# STM32.net
KiCad netlist of a schematic drawn in Altium Designer
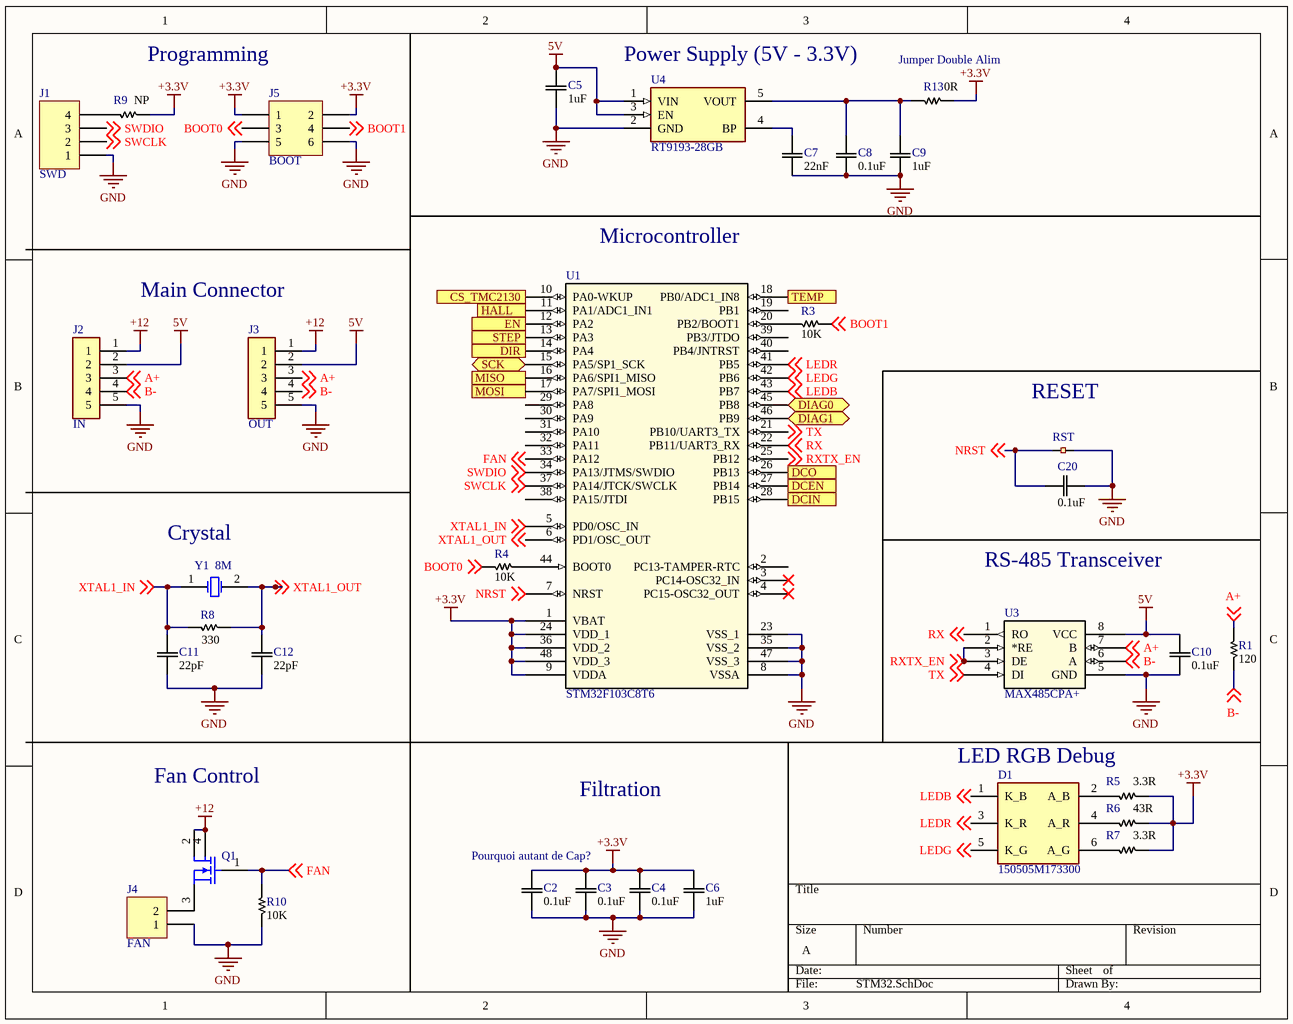
[diagram p0: STM32.SchDoc]

(export (version "E")
  (design (tool "Eeschema 10.0.6"))
  (components
    (comp (ref "C2")
      (value "0.1uF")
      (footprint "0603")
      (description "Capacitor SMD 1206")
      (fields
        (field (name "MANUFACTURER_PART_NUMBER") "12065A820JAT2A")
        (field (name "Comment") "Capacitor 1206")
        (field (name "COPYRIGHT") "Copyright (C) 2018 Accelerated Designs. All rights reserved")
      )
      (libsource (lib "Schematic_Emile") (part "Capacitor 1206"))
    )
    (comp (ref "C3")
      (value "0.1uF")
      (footprint "0603")
      (description "Capacitor SMD 1206")
      (fields
        (field (name "MANUFACTURER_PART_NUMBER") "12065A820JAT2A")
        (field (name "Comment") "Capacitor 1206")
        (field (name "COPYRIGHT") "Copyright (C) 2018 Accelerated Designs. All rights reserved")
      )
      (libsource (lib "Schematic_Emile") (part "Capacitor 1206"))
    )
    (comp (ref "C4")
      (value "0.1uF")
      (footprint "0603")
      (description "Capacitor SMD 1206")
      (fields
        (field (name "MANUFACTURER_PART_NUMBER") "12065A820JAT2A")
        (field (name "Comment") "Capacitor 1206")
        (field (name "COPYRIGHT") "Copyright (C) 2018 Accelerated Designs. All rights reserved")
      )
      (libsource (lib "Schematic_Emile") (part "Capacitor 1206"))
    )
    (comp (ref "C5")
      (value "1uF")
      (footprint "0603")
      (description "Capacitor SMD 1206")
      (fields
        (field (name "MANUFACTURER_PART_NUMBER") "12065A820JAT2A")
        (field (name "Comment") "Capacitor 1206")
        (field (name "COPYRIGHT") "Copyright (C) 2018 Accelerated Designs. All rights reserved")
      )
      (libsource (lib "Schematic_Emile") (part "Capacitor 1206"))
    )
    (comp (ref "C6")
      (value "1uF")
      (footprint "0603")
      (description "Capacitor SMD 1206")
      (fields
        (field (name "MANUFACTURER_PART_NUMBER") "12065A820JAT2A")
        (field (name "Comment") "Capacitor 1206")
        (field (name "COPYRIGHT") "Copyright (C) 2018 Accelerated Designs. All rights reserved")
      )
      (libsource (lib "Schematic_Emile") (part "Capacitor 1206"))
    )
    (comp (ref "C7")
      (value "22nF")
      (footprint "0603")
      (description "Capacitor SMD 1206")
      (fields
        (field (name "MANUFACTURER_PART_NUMBER") "12065A820JAT2A")
        (field (name "Comment") "Capacitor 1206")
        (field (name "COPYRIGHT") "Copyright (C) 2018 Accelerated Designs. All rights reserved")
      )
      (libsource (lib "Schematic_Emile") (part "Capacitor 1206"))
    )
    (comp (ref "C8")
      (value "0.1uF")
      (footprint "0603")
      (description "Capacitor SMD 1206")
      (fields
        (field (name "MANUFACTURER_PART_NUMBER") "12065A820JAT2A")
        (field (name "Comment") "Capacitor 1206")
        (field (name "COPYRIGHT") "Copyright (C) 2018 Accelerated Designs. All rights reserved")
      )
      (libsource (lib "Schematic_Emile") (part "Capacitor 1206"))
    )
    (comp (ref "C9")
      (value "1uF")
      (footprint "0603")
      (description "Capacitor SMD 1206")
      (fields
        (field (name "MANUFACTURER_PART_NUMBER") "12065A820JAT2A")
        (field (name "Comment") "Capacitor 1206")
        (field (name "COPYRIGHT") "Copyright (C) 2018 Accelerated Designs. All rights reserved")
      )
      (libsource (lib "Schematic_Emile") (part "Capacitor 1206"))
    )
    (comp (ref "C10")
      (value "0.1uF")
      (footprint "0603")
      (description "Capacitor SMD 1206")
      (fields
        (field (name "MANUFACTURER_PART_NUMBER") "12065A820JAT2A")
        (field (name "Comment") "Capacitor 1206")
        (field (name "COPYRIGHT") "Copyright (C) 2018 Accelerated Designs. All rights reserved")
      )
      (libsource (lib "Schematic_Emile") (part "Capacitor 1206"))
    )
    (comp (ref "C11")
      (value "22pF")
      (footprint "0603")
      (description "Capacitor SMD 1206")
      (fields
        (field (name "MANUFACTURER_PART_NUMBER") "12065A820JAT2A")
        (field (name "Comment") "Capacitor 1206")
        (field (name "COPYRIGHT") "Copyright (C) 2018 Accelerated Designs. All rights reserved")
      )
      (libsource (lib "Schematic_Emile") (part "Capacitor 1206"))
    )
    (comp (ref "C12")
      (value "22pF")
      (footprint "0603")
      (description "Capacitor SMD 1206")
      (fields
        (field (name "MANUFACTURER_PART_NUMBER") "12065A820JAT2A")
        (field (name "Comment") "Capacitor 1206")
        (field (name "COPYRIGHT") "Copyright (C) 2018 Accelerated Designs. All rights reserved")
      )
      (libsource (lib "Schematic_Emile") (part "Capacitor 1206"))
    )
    (comp (ref "C20")
      (value "0.1uF")
      (footprint "0603")
      (description "Capacitor SMD 1206")
      (fields
        (field (name "MANUFACTURER_PART_NUMBER") "12065A820JAT2A")
        (field (name "Comment") "Capacitor 1206")
        (field (name "COPYRIGHT") "Copyright (C) 2018 Accelerated Designs. All rights reserved")
      )
      (libsource (lib "Schematic_Emile") (part "Capacitor 1206"))
    )
    (comp (ref "D1")
      (value "150505M173300")
      (footprint "LED 5050")
      (description "LED")
      (fields
        (field (name "MOUSER PART NUMBER") "710-150505M173300")
        (field (name "RS PART NUMBER") "1766248P")
      )
      (libsource (lib "Schematic_Emile") (part "150505M173300"))
    )
    (comp (ref "J1")
      (value "SWD")
      (footprint "HDR1X4")
      (description "Header, 4-Pin")
      (fields (field (name "PUBLISHER") "Altium Limited"))
      (libsource (lib "Miscellaneous Connectors") (part "Header 4"))
    )
    (comp (ref "J2")
      (value "IN")
      (footprint "JST 5POS 2.5mm 90°")
      (description "Connector")
      (fields (field (name "MANUFACTURER_PART_NUMBER") "S5B-XH-A-1(LF)(SN)"))
      (libsource (lib "Schematic_Emile") (part "JST 5POS"))
    )
    (comp (ref "J3")
      (value "OUT")
      (footprint "JST 5POS 2.5mm 90°")
      (description "Connector")
      (fields (field (name "MANUFACTURER_PART_NUMBER") "S5B-XH-A-1(LF)(SN)"))
      (libsource (lib "Schematic_Emile") (part "JST 5POS"))
    )
    (comp (ref "J4")
      (value "FAN")
      (footprint "HDR1X2")
      (description "Header, 2-Pin")
      (fields (field (name "PUBLISHER") "Altium Limited"))
      (libsource (lib "Miscellaneous Connectors") (part "Header 2"))
    )
    (comp (ref "J5")
      (value "BOOT")
      (footprint "HDR2X3")
      (description "Header, 3-Pin, Dual row")
      (fields (field (name "PUBLISHER") "Altium Limited"))
      (libsource (lib "Miscellaneous Connectors") (part "Header 3X2"))
    )
    (comp (ref "Q1")
      (value "MOSFET N-CH")
      (footprint "SOT223_M")
      (description "55V 7A SOT223")
      (libsource (lib "Schematic_Emile") (part "MOSFET N-CH"))
    )
    (comp (ref "R1")
      (value "120")
      (footprint "0603")
      (description "Resistor 0603 SMD")
      (fields
        (field (name "MANUFACTURER_PART_NUMBER") "ERJ8CWFR024V")
        (field (name "Comment") "Resistor 0603")
        (field (name "COPYRIGHT") "Copyright (C) 2018 Accelerated Designs. All rights reserved")
      )
      (libsource (lib "Schematic_Emile") (part "Resistor 1206"))
    )
    (comp (ref "R3")
      (value "10K")
      (footprint "0603")
      (description "Resistor 1206 SMD")
      (fields
        (field (name "MANUFACTURER_PART_NUMBER") "ERJ8CWFR024V")
        (field (name "Comment") "Resistor 1206")
        (field (name "COPYRIGHT") "Copyright (C) 2018 Accelerated Designs. All rights reserved")
      )
      (libsource (lib "Schematic_Emile") (part "Resistor 1206"))
    )
    (comp (ref "R4")
      (value "10K")
      (footprint "0603")
      (description "Resistor 1206 SMD")
      (fields
        (field (name "MANUFACTURER_PART_NUMBER") "ERJ8CWFR024V")
        (field (name "Comment") "Resistor 1206")
        (field (name "COPYRIGHT") "Copyright (C) 2018 Accelerated Designs. All rights reserved")
      )
      (libsource (lib "Schematic_Emile") (part "Resistor 1206"))
    )
    (comp (ref "R5")
      (value "3.3R")
      (footprint "0603")
      (description "Resistor 0603 SMD")
      (fields
        (field (name "MANUFACTURER_PART_NUMBER") "ERJ8CWFR024V")
        (field (name "Comment") "Resistor 0603")
        (field (name "COPYRIGHT") "Copyright (C) 2018 Accelerated Designs. All rights reserved")
      )
      (libsource (lib "Schematic_Emile") (part "Resistor 1206"))
    )
    (comp (ref "R6")
      (value "43R")
      (footprint "0603")
      (description "Resistor 0603 SMD")
      (fields
        (field (name "MANUFACTURER_PART_NUMBER") "ERJ8CWFR024V")
        (field (name "Comment") "Resistor 0603")
        (field (name "COPYRIGHT") "Copyright (C) 2018 Accelerated Designs. All rights reserved")
      )
      (libsource (lib "Schematic_Emile") (part "Resistor 1206"))
    )
    (comp (ref "R7")
      (value "3.3R")
      (footprint "0603")
      (description "Resistor 0603 SMD")
      (fields
        (field (name "MANUFACTURER_PART_NUMBER") "ERJ8CWFR024V")
        (field (name "Comment") "Resistor 0603")
        (field (name "COPYRIGHT") "Copyright (C) 2018 Accelerated Designs. All rights reserved")
      )
      (libsource (lib "Schematic_Emile") (part "Resistor 1206"))
    )
    (comp (ref "R8")
      (value "330")
      (footprint "0603")
      (description "Resistor 0603 SMD")
      (fields
        (field (name "MANUFACTURER_PART_NUMBER") "ERJ8CWFR024V")
        (field (name "Comment") "Resistor 0603")
        (field (name "COPYRIGHT") "Copyright (C) 2018 Accelerated Designs. All rights reserved")
      )
      (libsource (lib "Schematic_Emile") (part "Resistor 1206"))
    )
    (comp (ref "R9")
      (value "NP")
      (footprint "0603")
      (description "Resistor 1206 SMD")
      (fields
        (field (name "MANUFACTURER_PART_NUMBER") "ERJ8CWFR024V")
        (field (name "Comment") "Jumper 0603")
        (field (name "COPYRIGHT") "Copyright (C) 2018 Accelerated Designs. All rights reserved")
      )
      (libsource (lib "Schematic_Emile") (part "Resistor 1206"))
    )
    (comp (ref "R10")
      (value "10K")
      (footprint "0603")
      (description "Resistor 0603 SMD")
      (fields
        (field (name "MANUFACTURER_PART_NUMBER") "ERJ8CWFR024V")
        (field (name "Comment") "Resistor 0603")
        (field (name "COPYRIGHT") "Copyright (C) 2018 Accelerated Designs. All rights reserved")
      )
      (libsource (lib "Schematic_Emile") (part "Resistor 1206"))
    )
    (comp (ref "R13")
      (value "0R")
      (footprint "0603")
      (description "Resistor 1206 SMD")
      (fields
        (field (name "MANUFACTURER_PART_NUMBER") "ERJ8CWFR024V")
        (field (name "Comment") "Jumper 0603")
        (field (name "COPYRIGHT") "Copyright (C) 2018 Accelerated Designs. All rights reserved")
      )
      (libsource (lib "Schematic_Emile") (part "Resistor 1206"))
    )
    (comp (ref "RST")
      (value "PAD")
      (footprint "PAD")
      (description "SMD Pad for contact")
      (libsource (lib "Schematic_Emile") (part "PAD"))
    )
    (comp (ref "U1")
      (value "STM32F103C8T6")
      (footprint "LQFP-48")
      (description "Integrated Circuit STM32")
      (fields (field (name "COPYRIGHT") "Copyright (C) 2018 Accelerated Designs. All rights reserved"))
      (libsource (lib "Schematic_Emile") (part "STM32F103C8T6"))
    )
    (comp (ref "U3")
      (value "MAX485CPA+")
      (footprint "DIP 8 - 3D")
      (description "RS485 Communication")
      (fields (field (name "COPYRIGHT") "Copyright (C) 2018 Accelerated Designs. All rights reserved"))
      (libsource (lib "Schematic_Emile") (part "MAX485CPA+"))
    )
    (comp (ref "U4")
      (value "RT9193-28GB")
      (footprint "SamacSys:SOT94P279X130-5N")
      (description "Voltage Regulator 3.3V")
      (libsource (lib "Schematic_Emile") (part "RT9193-28GB"))
    )
    (comp (ref "Y1")
      (value "8M")
      (footprint "ATS080B-E")
      (description "Crystal Oscillator")
      (fields (field (name "PUBLISHER") "Altium Limited"))
      (libsource (lib "Miscellaneous Devices") (part "XTAL"))
    )
  )
  (nets
    (net (code "1") (name "+3.3V") (class "Default")
      (node (ref "C2") (pin "2") (pinfunction "2_2") (pintype "passive"))
      (node (ref "C3") (pin "2") (pinfunction "2_2") (pintype "passive"))
      (node (ref "C4") (pin "2") (pinfunction "2_2") (pintype "passive"))
      (node (ref "C6") (pin "2") (pinfunction "2_2") (pintype "passive"))
      (node (ref "J5") (pin "1") (pinfunction "1_1") (pintype "passive"))
      (node (ref "J5") (pin "2") (pinfunction "2_2") (pintype "passive"))
      (node (ref "R13") (pin "2") (pinfunction "2_2") (pintype "passive"))
      (node (ref "R5") (pin "2") (pinfunction "2_2") (pintype "passive"))
      (node (ref "R6") (pin "2") (pinfunction "2_2") (pintype "passive"))
      (node (ref "R7") (pin "2") (pinfunction "2_2") (pintype "passive"))
      (node (ref "R9") (pin "2") (pinfunction "2_2") (pintype "passive"))
      (node (ref "U1") (pin "1") (pinfunction "VBAT_1") (pintype "power_in"))
      (node (ref "U1") (pin "24") (pinfunction "VDD_1_24") (pintype "power_in"))
      (node (ref "U1") (pin "36") (pinfunction "VDD_2_36") (pintype "power_in"))
      (node (ref "U1") (pin "48") (pinfunction "VDD_3_48") (pintype "power_in"))
      (node (ref "U1") (pin "9") (pinfunction "VDDA_9") (pintype "power_in"))
    )
    (net (code "2") (name "+12") (class "Default")
      (node (ref "J2") (pin "1") (pinfunction "1_1") (pintype "passive"))
      (node (ref "J3") (pin "1") (pinfunction "1_1") (pintype "passive"))
      (node (ref "Q1") (pin "2") (pinfunction "D_2") (pintype "passive"))
      (node (ref "Q1") (pin "4") (pinfunction "D_4") (pintype "passive"))
    )
    (net (code "3") (name "/CS_TMC2130") (class "Default")
      (node (ref "U1") (pin "10") (pinfunction "PA0-WKUP_10") (pintype "bidirectional"))
    )
    (net (code "4") (name "/DCEN") (class "Default")
      (node (ref "U1") (pin "27") (pinfunction "PB14_27") (pintype "bidirectional"))
    )
    (net (code "5") (name "/DCIN") (class "Default")
      (node (ref "U1") (pin "28") (pinfunction "PB15_28") (pintype "bidirectional"))
    )
    (net (code "6") (name "/DCO") (class "Default")
      (node (ref "U1") (pin "26") (pinfunction "PB13_26") (pintype "bidirectional"))
    )
    (net (code "7") (name "/DIAG0") (class "Default")
      (node (ref "U1") (pin "45") (pinfunction "PB8_45") (pintype "bidirectional"))
    )
    (net (code "8") (name "/DIAG1") (class "Default")
      (node (ref "U1") (pin "46") (pinfunction "PB9_46") (pintype "bidirectional"))
    )
    (net (code "9") (name "/DIR") (class "Default")
      (node (ref "U1") (pin "14") (pinfunction "PA4_14") (pintype "bidirectional"))
    )
    (net (code "10") (name "/EN") (class "Default")
      (node (ref "U1") (pin "12") (pinfunction "PA2_12") (pintype "bidirectional"))
    )
    (net (code "11") (name "/HALL") (class "Default")
      (node (ref "U1") (pin "11") (pinfunction "PA1/ADC1_IN1_11") (pintype "bidirectional"))
    )
    (net (code "12") (name "/MISO") (class "Default")
      (node (ref "U1") (pin "16") (pinfunction "PA6/SPI1_MISO_16") (pintype "bidirectional"))
    )
    (net (code "13") (name "/MOSI") (class "Default")
      (node (ref "U1") (pin "17") (pinfunction "PA7/SPI1_MOSI_17") (pintype "bidirectional"))
    )
    (net (code "14") (name "/SCK") (class "Default")
      (node (ref "U1") (pin "15") (pinfunction "PA5/SP1_SCK_15") (pintype "bidirectional"))
    )
    (net (code "15") (name "/STEP") (class "Default")
      (node (ref "U1") (pin "13") (pinfunction "PA3_13") (pintype "bidirectional"))
    )
    (net (code "16") (name "/TEMP") (class "Default")
      (node (ref "U1") (pin "18") (pinfunction "PB0/ADC1_IN8_18") (pintype "bidirectional"))
    )
    (net (code "17") (name "5V") (class "Default")
      (node (ref "C10") (pin "2") (pinfunction "2_2") (pintype "passive"))
      (node (ref "C5") (pin "2") (pinfunction "2_2") (pintype "passive"))
      (node (ref "J2") (pin "2") (pinfunction "2_2") (pintype "passive"))
      (node (ref "J3") (pin "2") (pinfunction "2_2") (pintype "passive"))
      (node (ref "U3") (pin "8") (pinfunction "VCC_8") (pintype "power_in"))
      (node (ref "U4") (pin "1") (pinfunction "VIN_1") (pintype "input"))
      (node (ref "U4") (pin "3") (pinfunction "EN_3") (pintype "input"))
    )
    (net (code "18") (name "A+") (class "Default")
      (node (ref "J2") (pin "3") (pinfunction "3_3") (pintype "passive"))
      (node (ref "J3") (pin "3") (pinfunction "3_3") (pintype "passive"))
      (node (ref "R1") (pin "2") (pinfunction "2_2") (pintype "passive"))
      (node (ref "U3") (pin "7") (pinfunction "B_7") (pintype "bidirectional"))
    )
    (net (code "19") (name "B-") (class "Default")
      (node (ref "J2") (pin "4") (pinfunction "4_4") (pintype "passive"))
      (node (ref "J3") (pin "4") (pinfunction "4_4") (pintype "passive"))
      (node (ref "R1") (pin "1") (pinfunction "1_1") (pintype "passive"))
      (node (ref "U3") (pin "6") (pinfunction "A_6") (pintype "bidirectional"))
    )
    (net (code "20") (name "BOOT0") (class "Default")
      (node (ref "J5") (pin "3") (pinfunction "3_3") (pintype "passive"))
      (node (ref "R4") (pin "1") (pinfunction "1_1") (pintype "passive"))
    )
    (net (code "21") (name "BOOT1") (class "Default")
      (node (ref "J5") (pin "4") (pinfunction "4_4") (pintype "passive"))
      (node (ref "R3") (pin "2") (pinfunction "2_2") (pintype "passive"))
    )
    (net (code "22") (name "FAN") (class "Default")
      (node (ref "Q1") (pin "1") (pinfunction "G_1") (pintype "passive"))
      (node (ref "R10") (pin "2") (pinfunction "2_2") (pintype "passive"))
      (node (ref "U1") (pin "33") (pinfunction "PA12_33") (pintype "bidirectional"))
    )
    (net (code "23") (name "GND") (class "Default")
      (node (ref "C10") (pin "1") (pinfunction "1_1") (pintype "passive"))
      (node (ref "C11") (pin "1") (pinfunction "1_1") (pintype "passive"))
      (node (ref "C12") (pin "1") (pinfunction "1_1") (pintype "passive"))
      (node (ref "C2") (pin "1") (pinfunction "1_1") (pintype "passive"))
      (node (ref "C20") (pin "1") (pinfunction "1_1") (pintype "passive"))
      (node (ref "C3") (pin "1") (pinfunction "1_1") (pintype "passive"))
      (node (ref "C4") (pin "1") (pinfunction "1_1") (pintype "passive"))
      (node (ref "C5") (pin "1") (pinfunction "1_1") (pintype "passive"))
      (node (ref "C6") (pin "1") (pinfunction "1_1") (pintype "passive"))
      (node (ref "C7") (pin "1") (pinfunction "1_1") (pintype "passive"))
      (node (ref "C8") (pin "1") (pinfunction "1_1") (pintype "passive"))
      (node (ref "C9") (pin "1") (pinfunction "1_1") (pintype "passive"))
      (node (ref "J1") (pin "1") (pinfunction "1_1") (pintype "passive"))
      (node (ref "J2") (pin "5") (pinfunction "5_5") (pintype "passive"))
      (node (ref "J3") (pin "5") (pinfunction "5_5") (pintype "passive"))
      (node (ref "J4") (pin "1") (pinfunction "1_1") (pintype "passive"))
      (node (ref "J5") (pin "5") (pinfunction "5_5") (pintype "passive"))
      (node (ref "J5") (pin "6") (pinfunction "6_6") (pintype "passive"))
      (node (ref "R10") (pin "1") (pinfunction "1_1") (pintype "passive"))
      (node (ref "RST") (pin "1") (pinfunction "1_1") (pintype "passive"))
      (node (ref "U1") (pin "23") (pinfunction "VSS_1_23") (pintype "power_in"))
      (node (ref "U1") (pin "35") (pinfunction "VSS_2_35") (pintype "power_in"))
      (node (ref "U1") (pin "47") (pinfunction "VSS_3_47") (pintype "power_in"))
      (node (ref "U1") (pin "8") (pinfunction "VSSA_8") (pintype "power_in"))
      (node (ref "U3") (pin "5") (pinfunction "GND_5") (pintype "power_in"))
      (node (ref "U4") (pin "2") (pinfunction "GND_2") (pintype "power_in"))
    )
    (net (code "24") (name "LEDB") (class "Default")
      (node (ref "D1") (pin "1") (pinfunction "K_B_1") (pintype "passive"))
      (node (ref "U1") (pin "43") (pinfunction "PB7_43") (pintype "bidirectional"))
    )
    (net (code "25") (name "LEDG") (class "Default")
      (node (ref "D1") (pin "5") (pinfunction "K_G_5") (pintype "passive"))
      (node (ref "U1") (pin "42") (pinfunction "PB6_42") (pintype "bidirectional"))
    )
    (net (code "26") (name "LEDR") (class "Default")
      (node (ref "D1") (pin "3") (pinfunction "K_R_3") (pintype "passive"))
      (node (ref "U1") (pin "41") (pinfunction "PB5_41") (pintype "bidirectional"))
    )
    (net (code "27") (name "NRST") (class "Default")
      (node (ref "C20") (pin "2") (pinfunction "2_2") (pintype "passive"))
      (node (ref "RST") (pin "2") (pinfunction "2_2") (pintype "passive"))
      (node (ref "U1") (pin "7") (pinfunction "NRST_7") (pintype "bidirectional"))
    )
    (net (code "28") (name "Net-(D1-A_B)") (class "Default")
      (node (ref "D1") (pin "2") (pinfunction "A_B_2") (pintype "passive"))
      (node (ref "R5") (pin "1") (pinfunction "1_1") (pintype "passive"))
    )
    (net (code "29") (name "Net-(D1-A_G)") (class "Default")
      (node (ref "D1") (pin "6") (pinfunction "A_G_6") (pintype "passive"))
      (node (ref "R7") (pin "1") (pinfunction "1_1") (pintype "passive"))
    )
    (net (code "30") (name "Net-(D1-A_R)") (class "Default")
      (node (ref "D1") (pin "4") (pinfunction "A_R_4") (pintype "passive"))
      (node (ref "R6") (pin "1") (pinfunction "1_1") (pintype "passive"))
    )
    (net (code "31") (name "Net-(J1-Pad4)") (class "Default")
      (node (ref "J1") (pin "4") (pinfunction "4_4") (pintype "passive"))
      (node (ref "R9") (pin "1") (pinfunction "1_1") (pintype "passive"))
    )
    (net (code "32") (name "Net-(Q1-S)") (class "Default")
      (node (ref "J4") (pin "2") (pinfunction "2_2") (pintype "passive"))
      (node (ref "Q1") (pin "3") (pinfunction "S_3") (pintype "passive"))
    )
    (net (code "33") (name "Net-(U1-BOOT0)") (class "Default")
      (node (ref "R4") (pin "2") (pinfunction "2_2") (pintype "passive"))
      (node (ref "U1") (pin "44") (pinfunction "BOOT0_44") (pintype "input"))
    )
    (net (code "34") (name "Net-(U1-PB2{slash}BOOT1)") (class "Default")
      (node (ref "R3") (pin "1") (pinfunction "1_1") (pintype "passive"))
      (node (ref "U1") (pin "20") (pinfunction "PB2/BOOT1_20") (pintype "bidirectional"))
    )
    (net (code "35") (name "Net-(U4-BP)") (class "Default")
      (node (ref "C7") (pin "2") (pinfunction "2_2") (pintype "passive"))
      (node (ref "U4") (pin "4") (pinfunction "BP_4") (pintype "passive"))
    )
    (net (code "36") (name "Net-(U4-VOUT)") (class "Default")
      (node (ref "C8") (pin "2") (pinfunction "2_2") (pintype "passive"))
      (node (ref "C9") (pin "2") (pinfunction "2_2") (pintype "passive"))
      (node (ref "R13") (pin "1") (pinfunction "1_1") (pintype "passive"))
      (node (ref "U4") (pin "5") (pinfunction "VOUT_5") (pintype "passive"))
    )
    (net (code "37") (name "RX") (class "Default")
      (node (ref "U1") (pin "22") (pinfunction "PB11/UART3_RX_22") (pintype "bidirectional"))
      (node (ref "U3") (pin "1") (pinfunction "RO_1") (pintype "output"))
    )
    (net (code "38") (name "RXTX_EN") (class "Default")
      (node (ref "U1") (pin "25") (pinfunction "PB12_25") (pintype "bidirectional"))
      (node (ref "U3") (pin "2") (pinfunction "*RE_2") (pintype "input"))
      (node (ref "U3") (pin "3") (pinfunction "DE_3") (pintype "input"))
    )
    (net (code "39") (name "SWCLK") (class "Default")
      (node (ref "J1") (pin "2") (pinfunction "2_2") (pintype "passive"))
      (node (ref "U1") (pin "37") (pinfunction "PA14/JTCK/SWCLK_37") (pintype "bidirectional"))
    )
    (net (code "40") (name "SWDIO") (class "Default")
      (node (ref "J1") (pin "3") (pinfunction "3_3") (pintype "passive"))
      (node (ref "U1") (pin "34") (pinfunction "PA13/JTMS/SWDIO_34") (pintype "bidirectional"))
    )
    (net (code "41") (name "TX") (class "Default")
      (node (ref "U1") (pin "21") (pinfunction "PB10/UART3_TX_21") (pintype "bidirectional"))
      (node (ref "U3") (pin "4") (pinfunction "DI_4") (pintype "input"))
    )
    (net (code "42") (name "XTAL1_IN") (class "Default")
      (node (ref "C11") (pin "2") (pinfunction "2_2") (pintype "passive"))
      (node (ref "R8") (pin "1") (pinfunction "1_1") (pintype "passive"))
      (node (ref "U1") (pin "5") (pinfunction "PD0/OSC_IN_5") (pintype "bidirectional"))
      (node (ref "Y1") (pin "1") (pinfunction "OSC1_1") (pintype "passive"))
    )
    (net (code "43") (name "XTAL1_OUT") (class "Default")
      (node (ref "C12") (pin "2") (pinfunction "2_2") (pintype "passive"))
      (node (ref "R8") (pin "2") (pinfunction "2_2") (pintype "passive"))
      (node (ref "U1") (pin "6") (pinfunction "PD1/OSC_OUT_6") (pintype "bidirectional"))
      (node (ref "Y1") (pin "2") (pinfunction "OSC2_2") (pintype "passive"))
    )
    (net (code "44") (name "unconnected-(U1-PA8-Pad29)") (class "Default")
      (node (ref "U1") (pin "29") (pinfunction "PA8_29") (pintype "bidirectional"))
    )
    (net (code "45") (name "unconnected-(U1-PA9-Pad30)") (class "Default")
      (node (ref "U1") (pin "30") (pinfunction "PA9_30") (pintype "bidirectional"))
    )
    (net (code "46") (name "unconnected-(U1-PA10-Pad31)") (class "Default")
      (node (ref "U1") (pin "31") (pinfunction "PA10_31") (pintype "bidirectional"))
    )
    (net (code "47") (name "unconnected-(U1-PA11-Pad32)") (class "Default")
      (node (ref "U1") (pin "32") (pinfunction "PA11_32") (pintype "bidirectional"))
    )
    (net (code "48") (name "unconnected-(U1-PA15{slash}JTDI-Pad38)") (class "Default")
      (node (ref "U1") (pin "38") (pinfunction "PA15/JTDI_38") (pintype "bidirectional"))
    )
    (net (code "49") (name "unconnected-(U1-PB1-Pad19)") (class "Default")
      (node (ref "U1") (pin "19") (pinfunction "PB1_19") (pintype "bidirectional"))
    )
    (net (code "50") (name "unconnected-(U1-PB3{slash}JTDO-Pad39)") (class "Default")
      (node (ref "U1") (pin "39") (pinfunction "PB3/JTDO_39") (pintype "bidirectional"))
    )
    (net (code "51") (name "unconnected-(U1-PB4{slash}JNTRST-Pad40)") (class "Default")
      (node (ref "U1") (pin "40") (pinfunction "PB4/JNTRST_40") (pintype "bidirectional"))
    )
    (net (code "52") (name "unconnected-(U1-PC13-TAMPER-RTC-Pad2)") (class "Default")
      (node (ref "U1") (pin "2") (pinfunction "PC13-TAMPER-RTC_2") (pintype "bidirectional"))
    )
    (net (code "53") (name "unconnected-(U1-PC14-OSC32_IN-Pad3)") (class "Default")
      (node (ref "U1") (pin "3") (pinfunction "PC14-OSC32_IN_3") (pintype "bidirectional+no_connect"))
    )
    (net (code "54") (name "unconnected-(U1-PC15-OSC32_OUT-Pad4)") (class "Default")
      (node (ref "U1") (pin "4") (pinfunction "PC15-OSC32_OUT_4") (pintype "bidirectional+no_connect"))
    )
  )
)
